# SVL-Light-It-Base.net
KiCad netlist of a schematic drawn in EAGLE
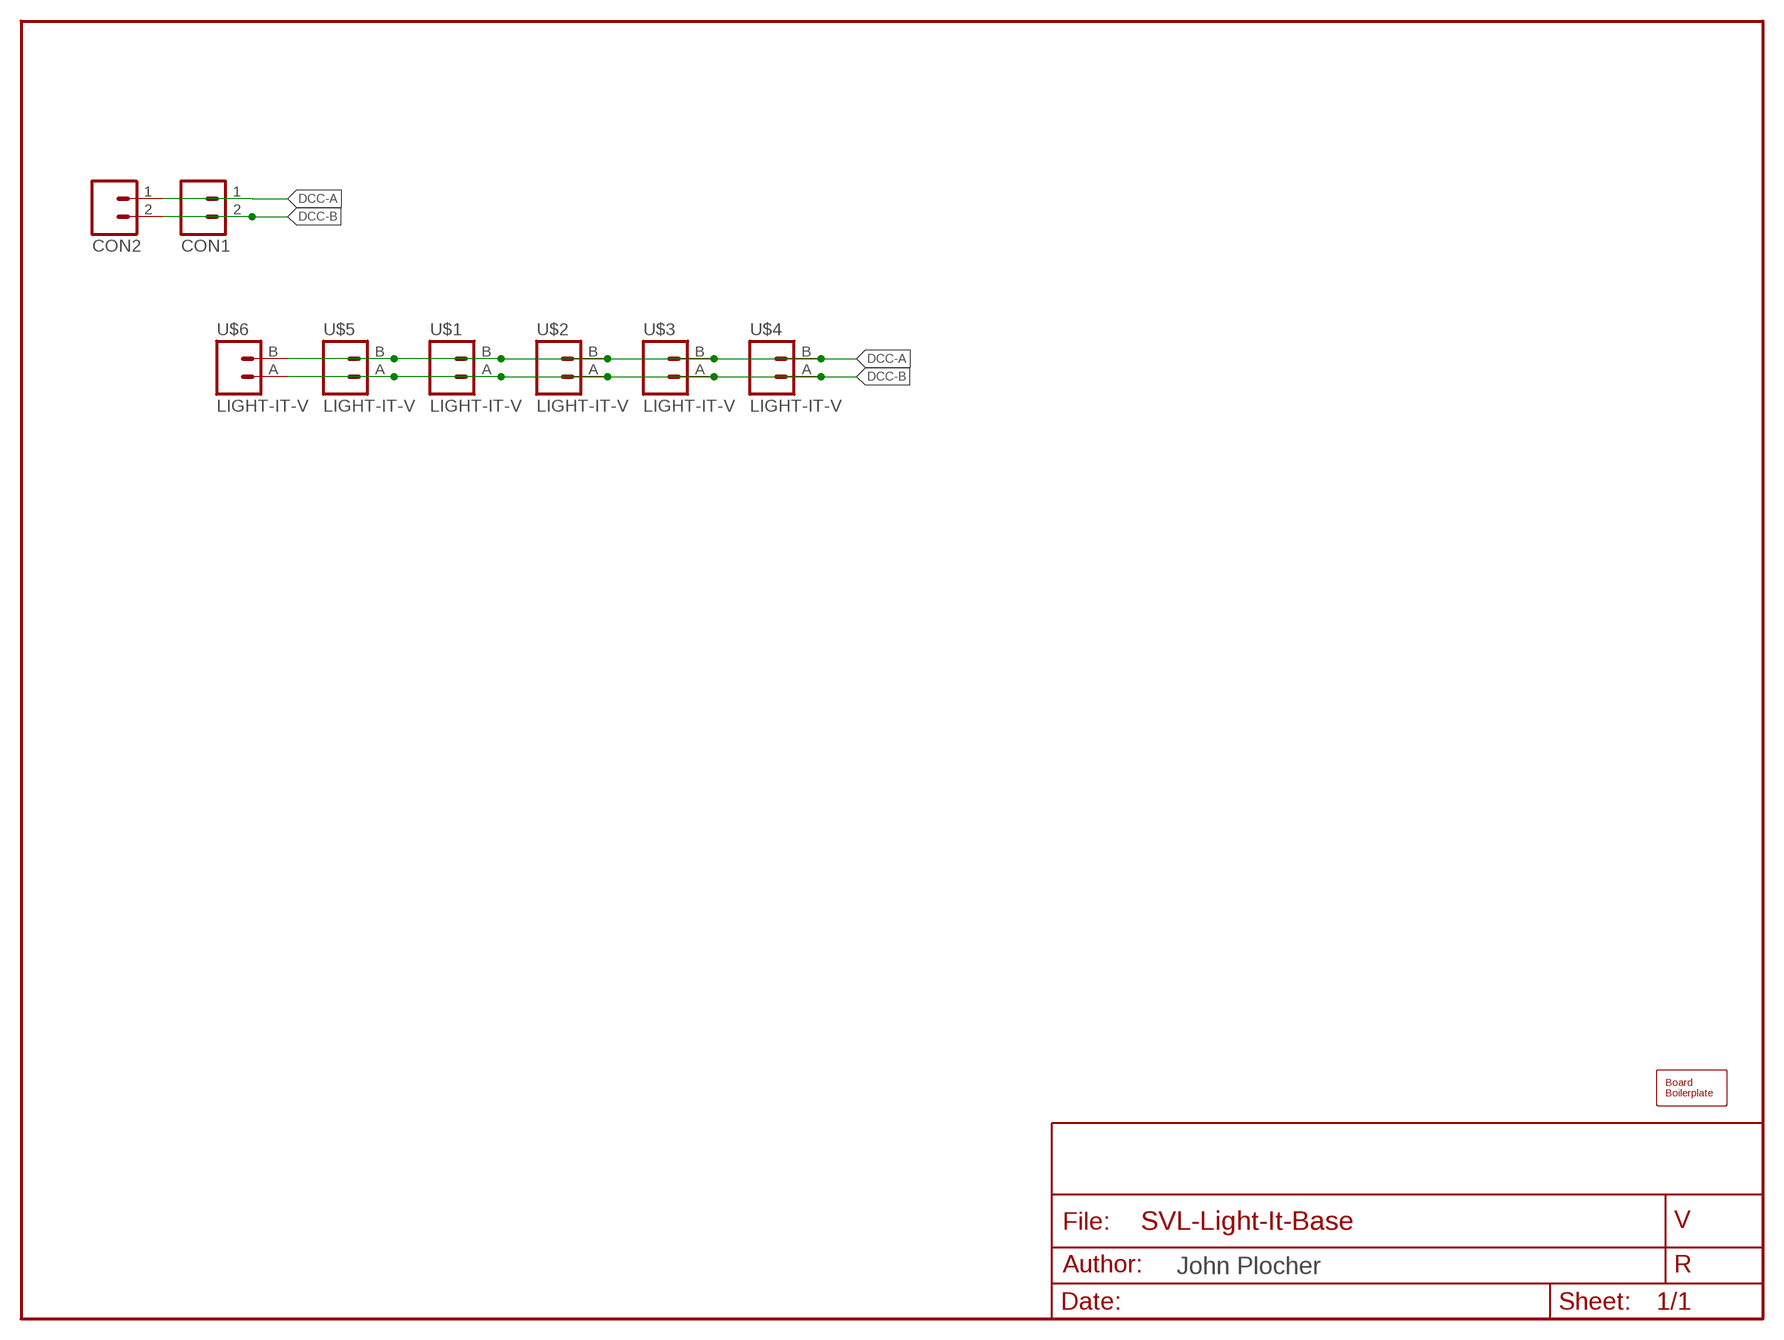
[diagram p0: schematic, sheet 1]

(export (version "E")
  (design (tool "Eeschema 10.0.6"))
  (components
    (comp (ref "BOARD1")
      (value "BOARD100X100")
      (footprint "eagle-import:BOARD-SEEED10X10")
      (libsource (lib "eagle-import") (part "BOARD100X100"))
    )
    (comp (ref "CON1")
      (value "CONNECTOR-M02508-LOCK")
      (footprint "eagle-import:MSTB2")
      (libsource (lib "eagle-import") (part "CONNECTOR-M02508-LOCK"))
    )
    (comp (ref "CON2")
      (value "CONNECTOR-M02508-LOCK")
      (footprint "eagle-import:MSTB2")
      (libsource (lib "eagle-import") (part "CONNECTOR-M02508-LOCK"))
    )
    (comp (ref "U$1")
      (value "LIGHT-IT-V")
      (footprint "eagle-import:LIGHT-IT-V")
      (libsource (lib "eagle-import") (part "LIGHT-IT-V"))
    )
    (comp (ref "U$2")
      (value "LIGHT-IT-V")
      (footprint "eagle-import:LIGHT-IT-V")
      (libsource (lib "eagle-import") (part "LIGHT-IT-V"))
    )
    (comp (ref "U$3")
      (value "LIGHT-IT-V")
      (footprint "eagle-import:LIGHT-IT-V")
      (libsource (lib "eagle-import") (part "LIGHT-IT-V"))
    )
    (comp (ref "U$4")
      (value "LIGHT-IT-V")
      (footprint "eagle-import:LIGHT-IT-V")
      (libsource (lib "eagle-import") (part "LIGHT-IT-V"))
    )
    (comp (ref "U$5")
      (value "LIGHT-IT-V")
      (footprint "eagle-import:LIGHT-IT-V")
      (libsource (lib "eagle-import") (part "LIGHT-IT-V"))
    )
    (comp (ref "U$6")
      (value "LIGHT-IT-V")
      (footprint "eagle-import:LIGHT-IT-V")
      (libsource (lib "eagle-import") (part "LIGHT-IT-V"))
    )
  )
  (nets
    (net (code "1") (name "DCC-A") (class "Default")
      (node (ref "CON1") (pin "1") (pinfunction "A_1") (pintype "passive"))
      (node (ref "CON2") (pin "1") (pinfunction "A_1") (pintype "passive"))
      (node (ref "U$1") (pin "B") (pinfunction "B_B") (pintype "passive"))
      (node (ref "U$2") (pin "B") (pinfunction "B_B") (pintype "passive"))
      (node (ref "U$3") (pin "B") (pinfunction "B_B") (pintype "passive"))
      (node (ref "U$4") (pin "B") (pinfunction "B_B") (pintype "passive"))
      (node (ref "U$5") (pin "B") (pinfunction "B_B") (pintype "passive"))
      (node (ref "U$6") (pin "B") (pinfunction "B_B") (pintype "passive"))
    )
    (net (code "2") (name "DCC-B") (class "Default")
      (node (ref "CON1") (pin "2") (pinfunction "B_2") (pintype "passive"))
      (node (ref "CON2") (pin "2") (pinfunction "B_2") (pintype "passive"))
      (node (ref "U$1") (pin "A") (pinfunction "A_A") (pintype "passive"))
      (node (ref "U$2") (pin "A") (pinfunction "A_A") (pintype "passive"))
      (node (ref "U$3") (pin "A") (pinfunction "A_A") (pintype "passive"))
      (node (ref "U$4") (pin "A") (pinfunction "A_A") (pintype "passive"))
      (node (ref "U$5") (pin "A") (pinfunction "A_A") (pintype "passive"))
      (node (ref "U$6") (pin "A") (pinfunction "A_A") (pintype "passive"))
    )
  )
)
